# ATTINY85_Updated_Design.net
KiCad netlist of a schematic drawn in EAGLE
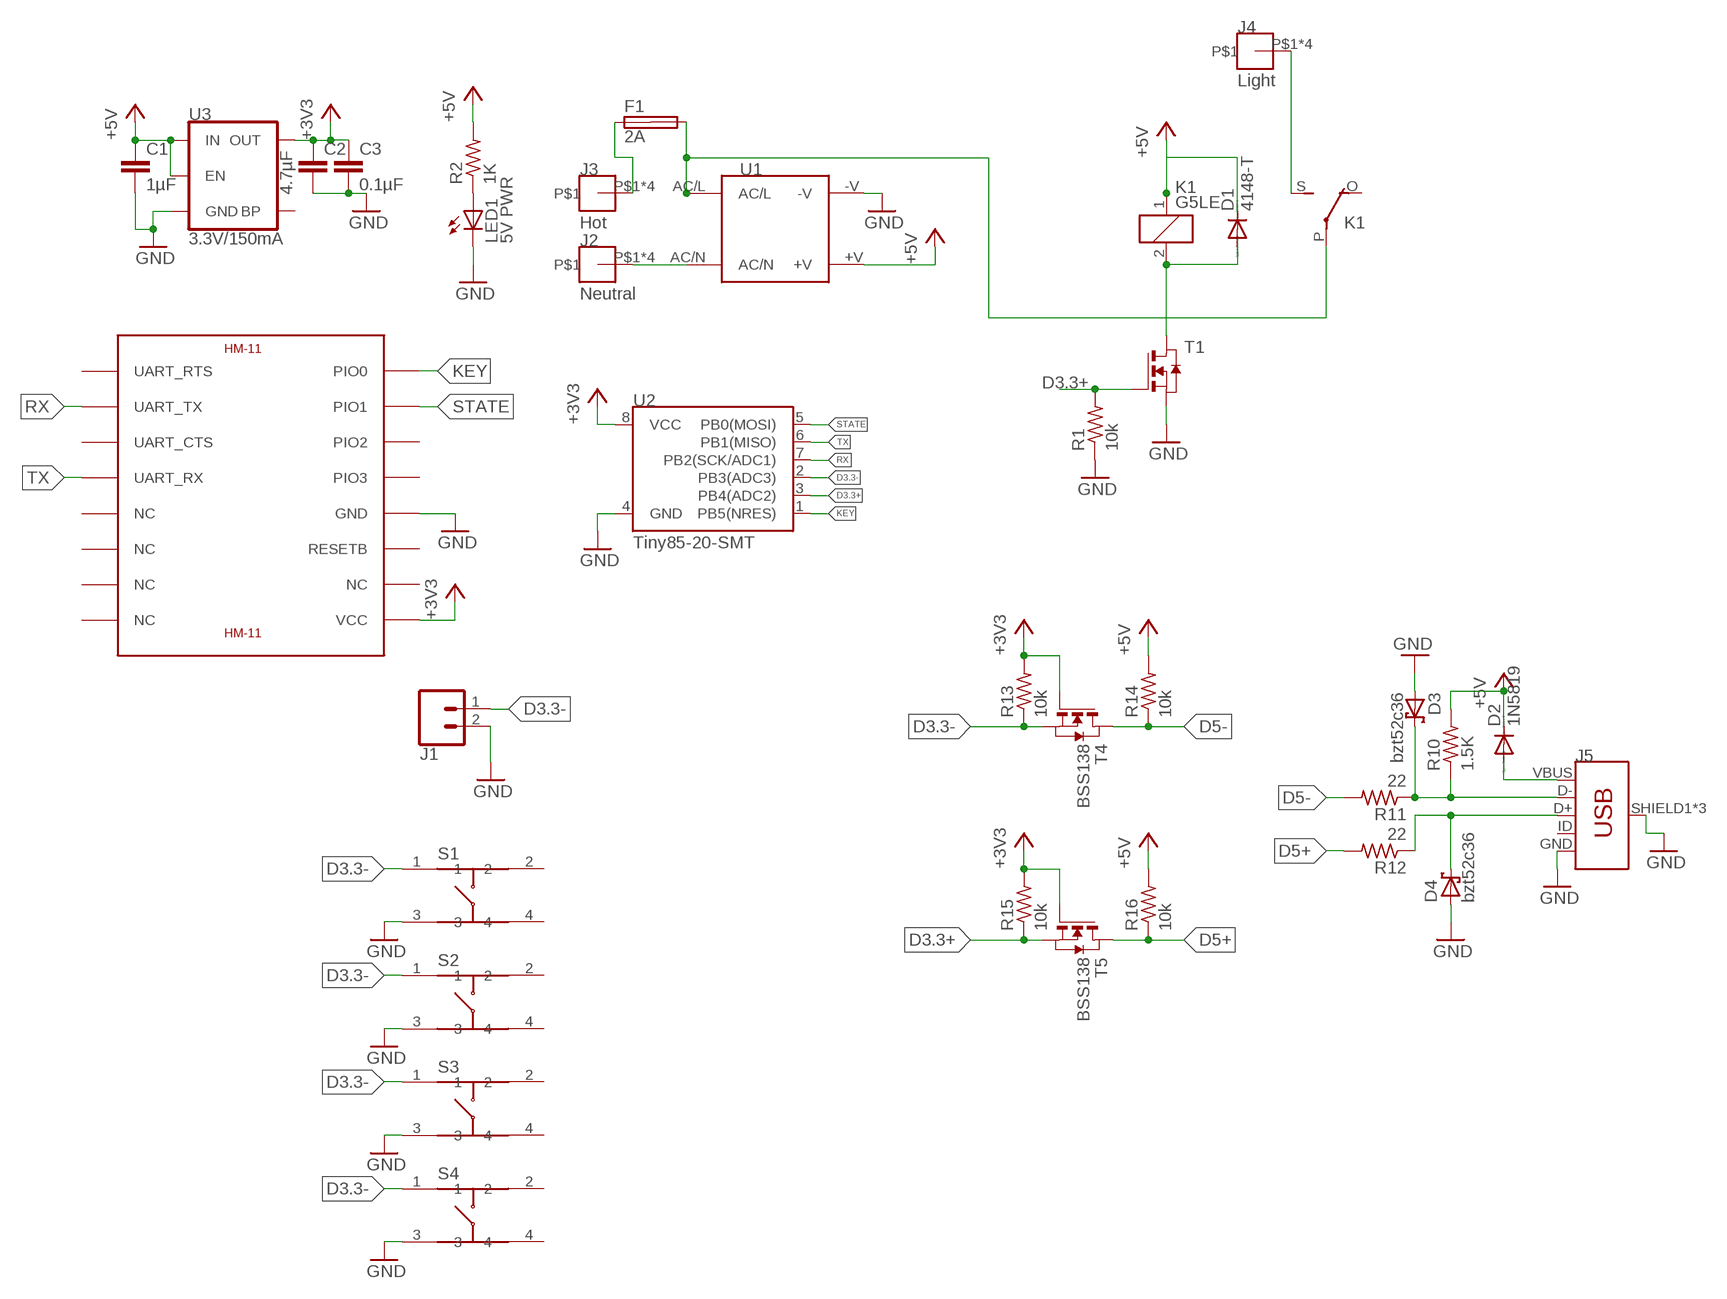
[diagram p0: schematic, sheet 1]

(export (version "E")
  (design (tool "Eeschema 10.0.6"))
  (components
    (comp (ref "C1")
      (value "1µF")
      (footprint "eagle-import:C0603K")
      (libsource (lib "eagle-import") (part "C-EUC0603K"))
    )
    (comp (ref "C2")
      (value "4.7µF")
      (footprint "eagle-import:C0603K")
      (libsource (lib "eagle-import") (part "C-EUC0603K"))
    )
    (comp (ref "C3")
      (value "0.1µF")
      (footprint "eagle-import:C0603K")
      (libsource (lib "eagle-import") (part "C-EUC0603K"))
    )
    (comp (ref "D1")
      (value "4148-T")
      (footprint "eagle-import:SOD80C")
      (libsource (lib "eagle-import") (part "DIODE-SOD80C"))
    )
    (comp (ref "D2")
      (value "1N5819")
      (footprint "eagle-import:SOD323-R")
      (libsource (lib "eagle-import") (part "DIODE-SOD323-R"))
    )
    (comp (ref "D3")
      (value "bzt52c36")
      (footprint "eagle-import:SOD323_ST")
      (libsource (lib "eagle-import") (part "BAT60J"))
    )
    (comp (ref "D4")
      (value "bzt52c36")
      (footprint "eagle-import:SOD323_ST")
      (libsource (lib "eagle-import") (part "BAT60J"))
    )
    (comp (ref "F1")
      (value "2A")
      (footprint "eagle-import:SHK20L")
      (libsource (lib "eagle-import") (part "SHK20L"))
    )
    (comp (ref "J1")
      (value "CONN_025MM")
      (footprint "eagle-import:SCREWTERMINAL-5MM-2")
      (libsource (lib "eagle-import") (part "CONN_025MM"))
    )
    (comp (ref "J2")
      (value "Neutral")
      (footprint "eagle-import:7700")
      (libsource (lib "eagle-import") (part "7700"))
    )
    (comp (ref "J3")
      (value "Hot")
      (footprint "eagle-import:7700")
      (libsource (lib "eagle-import") (part "7700"))
    )
    (comp (ref "J4")
      (value "Light")
      (footprint "eagle-import:7700")
      (libsource (lib "eagle-import") (part "7700"))
    )
    (comp (ref "J5")
      (value "USB_MICRO-B_FEMALE-SMT")
      (footprint "eagle-import:USB-B-MICRO-SMD")
      (libsource (lib "eagle-import") (part "USB_MICRO-B_FEMALE-SMT"))
    )
    (comp (ref "K1")
      (value "G5LE")
      (footprint "eagle-import:G5LE")
      (libsource (lib "eagle-import") (part "G5LE"))
    )
    (comp (ref "LED1")
      (value "5V PWR")
      (footprint "eagle-import:CHIPLED_0603")
      (libsource (lib "eagle-import") (part "LEDCHIPLED_0603"))
    )
    (comp (ref "R1")
      (value "10k")
      (footprint "eagle-import:R0603")
      (libsource (lib "eagle-import") (part "R-US_R0603"))
    )
    (comp (ref "R2")
      (value "1K")
      (footprint "eagle-import:R0603")
      (libsource (lib "eagle-import") (part "R-US_R0603"))
    )
    (comp (ref "R10")
      (value "1.5K")
      (footprint "eagle-import:R0603")
      (libsource (lib "eagle-import") (part "R-US_R0603"))
    )
    (comp (ref "R11")
      (value "22")
      (footprint "eagle-import:R0603")
      (libsource (lib "eagle-import") (part "R-US_R0603"))
    )
    (comp (ref "R12")
      (value "22")
      (footprint "eagle-import:R0603")
      (libsource (lib "eagle-import") (part "R-US_R0603"))
    )
    (comp (ref "R13")
      (value "10k")
      (footprint "eagle-import:R0603")
      (libsource (lib "eagle-import") (part "R-US_R0603"))
    )
    (comp (ref "R14")
      (value "10k")
      (footprint "eagle-import:R0603")
      (libsource (lib "eagle-import") (part "R-US_R0603"))
    )
    (comp (ref "R15")
      (value "10k")
      (footprint "eagle-import:R0603")
      (libsource (lib "eagle-import") (part "R-US_R0603"))
    )
    (comp (ref "R16")
      (value "10k")
      (footprint "eagle-import:R0603")
      (libsource (lib "eagle-import") (part "R-US_R0603"))
    )
    (comp (ref "S1")
      (value "PTS645S_SMTR92")
      (footprint "eagle-import:SMT")
      (libsource (lib "eagle-import") (part "PTS645S_SMTR92"))
    )
    (comp (ref "S2")
      (value "PTS645S_SMTR92")
      (footprint "eagle-import:SMT")
      (libsource (lib "eagle-import") (part "PTS645S_SMTR92"))
    )
    (comp (ref "S3")
      (value "PTS645S_SMTR92")
      (footprint "eagle-import:SMT")
      (libsource (lib "eagle-import") (part "PTS645S_SMTR92"))
    )
    (comp (ref "S4")
      (value "PTS645S_SMTR92")
      (footprint "eagle-import:SMT")
      (libsource (lib "eagle-import") (part "PTS645S_SMTR92"))
    )
    (comp (ref "T1")
      (value "NMOSSOT23")
      (footprint "eagle-import:SOT-23")
      (libsource (lib "eagle-import") (part "NMOSSOT23"))
    )
    (comp (ref "T4")
      (value "BSS138")
      (footprint "eagle-import:SOT-23")
      (libsource (lib "eagle-import") (part "NMOSSOT23"))
    )
    (comp (ref "T5")
      (value "BSS138")
      (footprint "eagle-import:SOT-23")
      (libsource (lib "eagle-import") (part "NMOSSOT23"))
    )
    (comp (ref "U$1")
      (value "HM-11")
      (footprint "eagle-import:HM-11")
      (libsource (lib "eagle-import") (part "HM-11"))
    )
    (comp (ref "U1")
      (value "IRM-05-5")
      (footprint "eagle-import:IRM-05")
      (libsource (lib "eagle-import") (part "IRM-05-5"))
    )
    (comp (ref "U2")
      (value "Tiny85-20-SMT")
      (footprint "eagle-import:SO08-EIAJ_MCU")
      (libsource (lib "eagle-import") (part "ATTINY45TINY85-20-SMT"))
    )
    (comp (ref "U3")
      (value "3.3V/150mA")
      (footprint "eagle-import:SOT23-5")
      (libsource (lib "eagle-import") (part "V_REG_MIC52053.3V"))
    )
  )
  (nets
    (net (code "1") (name "+3V3") (class "Default")
      (node (ref "C2") (pin "1") (pinfunction "1_1") (pintype "passive"))
      (node (ref "C3") (pin "1") (pinfunction "1_1") (pintype "passive"))
      (node (ref "R13") (pin "2") (pinfunction "2_2") (pintype "passive"))
      (node (ref "R15") (pin "2") (pinfunction "2_2") (pintype "passive"))
      (node (ref "T4") (pin "3") (pinfunction "G_3") (pintype "passive"))
      (node (ref "T5") (pin "3") (pinfunction "G_3") (pintype "passive"))
      (node (ref "U$1") (pin "VCC") (pinfunction "VCC_VCC") (pintype "bidirectional"))
      (node (ref "U2") (pin "8") (pinfunction "VCC_8") (pintype "bidirectional"))
      (node (ref "U3") (pin "5") (pinfunction "OUT_5") (pintype "passive"))
    )
    (net (code "2") (name "+5V") (class "Default")
      (node (ref "C1") (pin "1") (pinfunction "1_1") (pintype "passive"))
      (node (ref "D1") (pin "C") (pinfunction "C_C") (pintype "passive"))
      (node (ref "D2") (pin "C") (pinfunction "C_C") (pintype "passive"))
      (node (ref "K1") (pin "1") (pinfunction "1_1") (pintype "passive"))
      (node (ref "R10") (pin "2") (pinfunction "2_2") (pintype "passive"))
      (node (ref "R14") (pin "2") (pinfunction "2_2") (pintype "passive"))
      (node (ref "R16") (pin "2") (pinfunction "2_2") (pintype "passive"))
      (node (ref "R2") (pin "2") (pinfunction "2_2") (pintype "passive"))
      (node (ref "U1") (pin "+V") (pinfunction "+V_+V") (pintype "passive"))
      (node (ref "U3") (pin "1") (pinfunction "IN_1") (pintype "input"))
      (node (ref "U3") (pin "3") (pinfunction "EN_3") (pintype "input"))
    )
    (net (code "3") (name "D3.3+") (class "Default")
      (node (ref "R1") (pin "2") (pinfunction "2_2") (pintype "passive"))
      (node (ref "R15") (pin "1") (pinfunction "1_1") (pintype "passive"))
      (node (ref "T1") (pin "3") (pinfunction "G_3") (pintype "passive"))
      (node (ref "T5") (pin "2") (pinfunction "S_2") (pintype "passive"))
      (node (ref "U2") (pin "3") (pinfunction "PB4(ADC2)_3") (pintype "bidirectional"))
    )
    (net (code "4") (name "D3.3-") (class "Default")
      (node (ref "J1") (pin "1") (pinfunction "1_1") (pintype "passive"))
      (node (ref "R13") (pin "1") (pinfunction "1_1") (pintype "passive"))
      (node (ref "S1") (pin "1") (pinfunction "1_1") (pintype "bidirectional"))
      (node (ref "S2") (pin "1") (pinfunction "1_1") (pintype "bidirectional"))
      (node (ref "S3") (pin "1") (pinfunction "1_1") (pintype "bidirectional"))
      (node (ref "S4") (pin "1") (pinfunction "1_1") (pintype "bidirectional"))
      (node (ref "T4") (pin "2") (pinfunction "S_2") (pintype "passive"))
      (node (ref "U2") (pin "2") (pinfunction "PB3(ADC3)_2") (pintype "bidirectional"))
    )
    (net (code "5") (name "D5+") (class "Default")
      (node (ref "R12") (pin "2") (pinfunction "2_2") (pintype "passive"))
      (node (ref "R16") (pin "1") (pinfunction "1_1") (pintype "passive"))
      (node (ref "T5") (pin "1") (pinfunction "D_1") (pintype "passive"))
    )
    (net (code "6") (name "D5-") (class "Default")
      (node (ref "R11") (pin "2") (pinfunction "2_2") (pintype "passive"))
      (node (ref "R14") (pin "1") (pinfunction "1_1") (pintype "passive"))
      (node (ref "T4") (pin "1") (pinfunction "D_1") (pintype "passive"))
    )
    (net (code "7") (name "GND") (class "Default")
      (node (ref "C1") (pin "2") (pinfunction "2_2") (pintype "passive"))
      (node (ref "C2") (pin "2") (pinfunction "2_2") (pintype "passive"))
      (node (ref "C3") (pin "2") (pinfunction "2_2") (pintype "passive"))
      (node (ref "D3") (pin "A") (pinfunction "A_A") (pintype "passive"))
      (node (ref "D4") (pin "A") (pinfunction "A_A") (pintype "passive"))
      (node (ref "J1") (pin "2") (pinfunction "2_2") (pintype "passive"))
      (node (ref "J5") (pin "GND") (pinfunction "GND_GND") (pintype "power_in"))
      (node (ref "J5") (pin "SHIELD1") (pinfunction "SHIELD_SHIELD1") (pintype "bidirectional"))
      (node (ref "J5") (pin "SHIELD2") (pinfunction "SHIELD_SHIELD2") (pintype "bidirectional"))
      (node (ref "J5") (pin "SHIELD3") (pinfunction "SHIELD_SHIELD3") (pintype "bidirectional"))
      (node (ref "LED1") (pin "C") (pinfunction "C_C") (pintype "passive"))
      (node (ref "R1") (pin "1") (pinfunction "1_1") (pintype "passive"))
      (node (ref "S1") (pin "3") (pinfunction "3_3") (pintype "bidirectional"))
      (node (ref "S2") (pin "3") (pinfunction "3_3") (pintype "bidirectional"))
      (node (ref "S3") (pin "3") (pinfunction "3_3") (pintype "bidirectional"))
      (node (ref "S4") (pin "3") (pinfunction "3_3") (pintype "bidirectional"))
      (node (ref "T1") (pin "2") (pinfunction "S_2") (pintype "passive"))
      (node (ref "U$1") (pin "GND") (pinfunction "GND_GND") (pintype "bidirectional"))
      (node (ref "U1") (pin "-V") (pinfunction "-V_-V") (pintype "power_in"))
      (node (ref "U2") (pin "4") (pinfunction "GND_4") (pintype "bidirectional"))
      (node (ref "U3") (pin "2") (pinfunction "GND_2") (pintype "input"))
    )
    (net (code "8") (name "KEY") (class "Default")
      (node (ref "U$1") (pin "PIO0") (pinfunction "PIO0_PIO0") (pintype "bidirectional"))
      (node (ref "U2") (pin "1") (pinfunction "PB5(NRES)_1") (pintype "bidirectional"))
    )
    (net (code "9") (name "Net-(D2-PadA)") (class "Default")
      (node (ref "D2") (pin "A") (pinfunction "A_A") (pintype "passive"))
      (node (ref "J5") (pin "VBUS") (pinfunction "VBUS_VBUS") (pintype "power_in"))
    )
    (net (code "10") (name "Net-(D3-PadC)") (class "Default")
      (node (ref "D3") (pin "C") (pinfunction "C_C") (pintype "passive"))
      (node (ref "J5") (pin "D-") (pinfunction "D-_D-") (pintype "bidirectional"))
      (node (ref "R10") (pin "1") (pinfunction "1_1") (pintype "passive"))
      (node (ref "R11") (pin "1") (pinfunction "1_1") (pintype "passive"))
    )
    (net (code "11") (name "Net-(D4-PadC)") (class "Default")
      (node (ref "D4") (pin "C") (pinfunction "C_C") (pintype "passive"))
      (node (ref "J5") (pin "D+") (pinfunction "D+_D+") (pintype "bidirectional"))
      (node (ref "R12") (pin "1") (pinfunction "1_1") (pintype "passive"))
    )
    (net (code "12") (name "Net-(F1-Pad1A)") (class "Default")
      (node (ref "F1") (pin "1A") (pinfunction "1A_1A") (pintype "passive"))
      (node (ref "J3") (pin "P$1") (pinfunction "P$1_P$1") (pintype "bidirectional"))
      (node (ref "J3") (pin "P$2") (pinfunction "P$1_P$2") (pintype "bidirectional"))
      (node (ref "J3") (pin "P$3") (pinfunction "P$1_P$3") (pintype "bidirectional"))
      (node (ref "J3") (pin "P$4") (pinfunction "P$1_P$4") (pintype "bidirectional"))
    )
    (net (code "13") (name "Net-(F1-Pad2A)") (class "Default")
      (node (ref "F1") (pin "2A") (pinfunction "2A_2A") (pintype "passive"))
      (node (ref "K1") (pin "P") (pinfunction "P_P") (pintype "passive"))
      (node (ref "U1") (pin "AC/L") (pinfunction "AC/L_AC/L") (pintype "power_in"))
    )
    (net (code "14") (name "Net-(J2-P$1-PadP$2)") (class "Default")
      (node (ref "J2") (pin "P$1") (pinfunction "P$1_P$1") (pintype "bidirectional"))
      (node (ref "J2") (pin "P$2") (pinfunction "P$1_P$2") (pintype "bidirectional"))
      (node (ref "J2") (pin "P$3") (pinfunction "P$1_P$3") (pintype "bidirectional"))
      (node (ref "J2") (pin "P$4") (pinfunction "P$1_P$4") (pintype "bidirectional"))
      (node (ref "U1") (pin "AC/N") (pinfunction "AC/N_AC/N") (pintype "power_in"))
    )
    (net (code "15") (name "Net-(J4-P$1-PadP$2)") (class "Default")
      (node (ref "J4") (pin "P$1") (pinfunction "P$1_P$1") (pintype "bidirectional"))
      (node (ref "J4") (pin "P$2") (pinfunction "P$1_P$2") (pintype "bidirectional"))
      (node (ref "J4") (pin "P$3") (pinfunction "P$1_P$3") (pintype "bidirectional"))
      (node (ref "J4") (pin "P$4") (pinfunction "P$1_P$4") (pintype "bidirectional"))
      (node (ref "K1") (pin "S") (pinfunction "S_S") (pintype "passive"))
    )
    (net (code "16") (name "Net-(LED1-PadA)") (class "Default")
      (node (ref "LED1") (pin "A") (pinfunction "A_A") (pintype "passive"))
      (node (ref "R2") (pin "1") (pinfunction "1_1") (pintype "passive"))
    )
    (net (code "17") (name "Net-(T1-D)") (class "Default")
      (node (ref "D1") (pin "A") (pinfunction "A_A") (pintype "passive"))
      (node (ref "K1") (pin "2") (pinfunction "2_2") (pintype "passive"))
      (node (ref "T1") (pin "1") (pinfunction "D_1") (pintype "passive"))
    )
    (net (code "18") (name "RX") (class "Default")
      (node (ref "U$1") (pin "UART_TX") (pinfunction "UART_TX_UART_TX") (pintype "bidirectional"))
      (node (ref "U2") (pin "7") (pinfunction "PB2(SCK/ADC1)_7") (pintype "bidirectional"))
    )
    (net (code "19") (name "STATE") (class "Default")
      (node (ref "U$1") (pin "PIO1") (pinfunction "PIO1_PIO1") (pintype "bidirectional"))
      (node (ref "U2") (pin "5") (pinfunction "PB0(MOSI)_5") (pintype "bidirectional"))
    )
    (net (code "20") (name "TX") (class "Default")
      (node (ref "U$1") (pin "UART_RX") (pinfunction "UART_RX_UART_RX") (pintype "bidirectional"))
      (node (ref "U2") (pin "6") (pinfunction "PB1(MISO)_6") (pintype "bidirectional"))
    )
    (net (code "21") (name "unconnected-(F1-Pad1B)") (class "Default")
      (node (ref "F1") (pin "1B") (pinfunction "1B_1B") (pintype "passive"))
    )
    (net (code "22") (name "unconnected-(F1-Pad2B)") (class "Default")
      (node (ref "F1") (pin "2B") (pinfunction "2B_2B") (pintype "passive"))
    )
    (net (code "23") (name "unconnected-(J5-PadID)") (class "Default")
      (node (ref "J5") (pin "ID") (pinfunction "ID_ID") (pintype "bidirectional"))
    )
    (net (code "24") (name "unconnected-(K1-PadO)") (class "Default")
      (node (ref "K1") (pin "O") (pinfunction "O_O") (pintype "passive"))
    )
    (net (code "25") (name "unconnected-(S1-Pad2)") (class "Default")
      (node (ref "S1") (pin "2") (pinfunction "2_2") (pintype "bidirectional"))
    )
    (net (code "26") (name "unconnected-(S1-Pad4)") (class "Default")
      (node (ref "S1") (pin "4") (pinfunction "4_4") (pintype "bidirectional"))
    )
    (net (code "27") (name "unconnected-(S2-Pad2)") (class "Default")
      (node (ref "S2") (pin "2") (pinfunction "2_2") (pintype "bidirectional"))
    )
    (net (code "28") (name "unconnected-(S2-Pad4)") (class "Default")
      (node (ref "S2") (pin "4") (pinfunction "4_4") (pintype "bidirectional"))
    )
    (net (code "29") (name "unconnected-(S3-Pad2)") (class "Default")
      (node (ref "S3") (pin "2") (pinfunction "2_2") (pintype "bidirectional"))
    )
    (net (code "30") (name "unconnected-(S3-Pad4)") (class "Default")
      (node (ref "S3") (pin "4") (pinfunction "4_4") (pintype "bidirectional"))
    )
    (net (code "31") (name "unconnected-(S4-Pad2)") (class "Default")
      (node (ref "S4") (pin "2") (pinfunction "2_2") (pintype "bidirectional"))
    )
    (net (code "32") (name "unconnected-(S4-Pad4)") (class "Default")
      (node (ref "S4") (pin "4") (pinfunction "4_4") (pintype "bidirectional"))
    )
    (net (code "33") (name "unconnected-(U$1-NC-PadNC@5)") (class "Default")
      (node (ref "U$1") (pin "NC@5") (pinfunction "NC_NC@5") (pintype "bidirectional"))
    )
    (net (code "34") (name "unconnected-(U$1-NC-PadNC@6)") (class "Default")
      (node (ref "U$1") (pin "NC@6") (pinfunction "NC_NC@6") (pintype "bidirectional"))
    )
    (net (code "35") (name "unconnected-(U$1-NC-PadNC@7)") (class "Default")
      (node (ref "U$1") (pin "NC@7") (pinfunction "NC_NC@7") (pintype "bidirectional"))
    )
    (net (code "36") (name "unconnected-(U$1-NC-PadNC@8)") (class "Default")
      (node (ref "U$1") (pin "NC@8") (pinfunction "NC_NC@8") (pintype "bidirectional"))
    )
    (net (code "37") (name "unconnected-(U$1-NC-PadNC@10)") (class "Default")
      (node (ref "U$1") (pin "NC@10") (pinfunction "NC_NC@10") (pintype "bidirectional"))
    )
    (net (code "38") (name "unconnected-(U$1-PadPIO2)") (class "Default")
      (node (ref "U$1") (pin "PIO2") (pinfunction "PIO2_PIO2") (pintype "bidirectional"))
    )
    (net (code "39") (name "unconnected-(U$1-PadPIO3)") (class "Default")
      (node (ref "U$1") (pin "PIO3") (pinfunction "PIO3_PIO3") (pintype "bidirectional"))
    )
    (net (code "40") (name "unconnected-(U$1-PadRESETB)") (class "Default")
      (node (ref "U$1") (pin "RESETB") (pinfunction "RESETB_RESETB") (pintype "bidirectional"))
    )
    (net (code "41") (name "unconnected-(U$1-PadUART_CTS)") (class "Default")
      (node (ref "U$1") (pin "UART_CTS") (pinfunction "UART_CTS_UART_CTS") (pintype "bidirectional"))
    )
    (net (code "42") (name "unconnected-(U$1-PadUART_RTS)") (class "Default")
      (node (ref "U$1") (pin "UART_RTS") (pinfunction "UART_RTS_UART_RTS") (pintype "bidirectional"))
    )
    (net (code "43") (name "unconnected-(U3-BP-Pad4)") (class "Default")
      (node (ref "U3") (pin "4") (pinfunction "BP_4") (pintype "input"))
    )
  )
)
